# Eload_Gen_3_Power_Module_-_User_Inferfac.net
KiCad netlist of a schematic drawn in Altium Designer
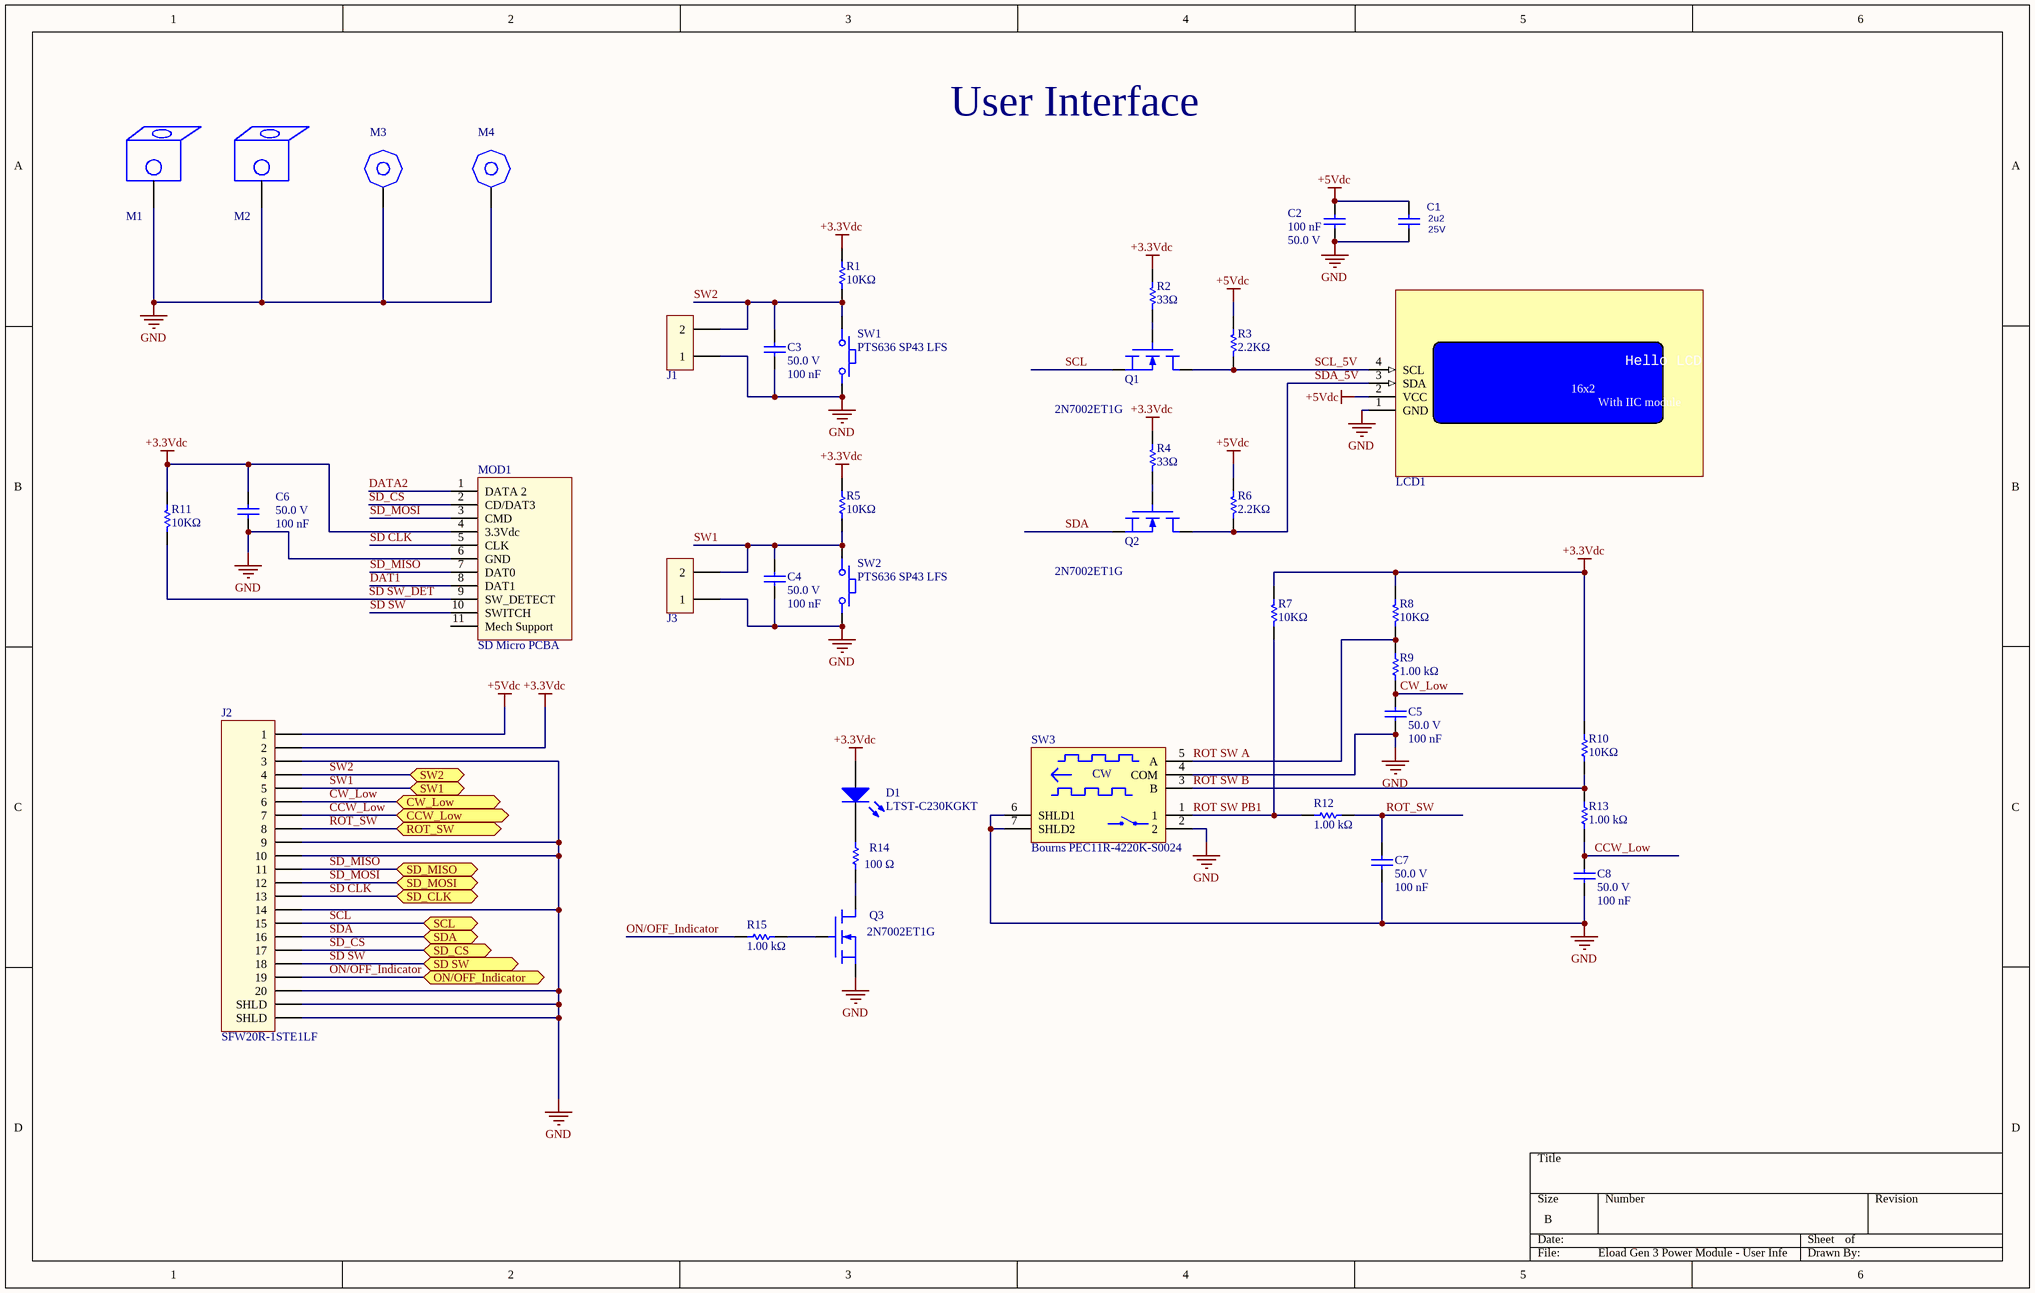
[diagram p0: Eload Gen 3 Power Module - User Inferface.SchDoc]

(export (version "E")
  (design (tool "Eeschema 10.0.6"))
  (components
    (comp (ref "C1")
      (value "2u2")
      (footprint "CAP, 0805, HD")
      (description "Cap,SMD,MLCC,2.2uF 25V X7R 10%,0805")
      (fields (field (name "MANUFACTURER") "Murata") (field (name "VOLTAGE") "25V"))
      (libsource (lib "Master SEPT2019") (part "Cap,0805,2.2uF,10%,25V"))
    )
    (comp (ref "C2")
      (value "08055C104JAT2A")
      (footprint "Cap,0805")
      (description "Capacitor; Ceramic; Cap 0.1 uF; Tol 5%; Vol-Rtg 50 VDC; SMT; 0805; X7R; Tape & Reel")
      (fields (field (name "VOLTAGE RATING (DC)") "50.0 V") (field (name "CAPACITANCE") "100 nF"))
      (libsource (lib "Master JULY2019") (part "Cap,0805,100nf,50V,5%,08055C104JAT2A"))
    )
    (comp (ref "C3")
      (value "08055C104JAT2A")
      (footprint "CAP, 0805, HD")
      (description "Capacitor; Ceramic; Cap 0.1 uF; Tol 5%; Vol-Rtg 50 VDC; SMT; 0805; X7R; Tape & Reel")
      (fields (field (name "VOLTAGE RATING (DC)") "50.0 V") (field (name "CAPACITANCE") "100 nF"))
      (libsource (lib "Master JULY2019") (part "Cap,0805,100nf,50V,5%,08055C104JAT2A"))
    )
    (comp (ref "C4")
      (value "08055C104JAT2A")
      (footprint "CAP, 0805, HD")
      (description "Capacitor; Ceramic; Cap 0.1 uF; Tol 5%; Vol-Rtg 50 VDC; SMT; 0805; X7R; Tape & Reel")
      (fields (field (name "VOLTAGE RATING (DC)") "50.0 V") (field (name "CAPACITANCE") "100 nF"))
      (libsource (lib "Master JULY2019") (part "Cap,0805,100nf,50V,5%,08055C104JAT2A"))
    )
    (comp (ref "C5")
      (value "08055C104JAT2A")
      (footprint "CAP, 0805, HD")
      (description "Capacitor; Ceramic; Cap 0.1 uF; Tol 5%; Vol-Rtg 50 VDC; SMT; 0805; X7R; Tape & Reel")
      (fields (field (name "VOLTAGE RATING (DC)") "50.0 V") (field (name "CAPACITANCE") "100 nF"))
      (libsource (lib "Master JULY2019") (part "Cap,0805,100nf,50V,5%,08055C104JAT2A"))
    )
    (comp (ref "C6")
      (value "08055C104JAT2A")
      (footprint "Cap,0805")
      (description "Capacitor; Ceramic; Cap 0.1 uF; Tol 5%; Vol-Rtg 50 VDC; SMT; 0805; X7R; Tape & Reel")
      (fields (field (name "VOLTAGE RATING (DC)") "50.0 V") (field (name "CAPACITANCE") "100 nF"))
      (libsource (lib "Master JULY2019") (part "Cap,0805,100nf,50V,5%,08055C104JAT2A"))
    )
    (comp (ref "C7")
      (value "08055C104JAT2A")
      (footprint "CAP, 0805, HD")
      (description "Capacitor; Ceramic; Cap 0.1 uF; Tol 5%; Vol-Rtg 50 VDC; SMT; 0805; X7R; Tape & Reel")
      (fields (field (name "VOLTAGE RATING (DC)") "50.0 V") (field (name "CAPACITANCE") "100 nF"))
      (libsource (lib "Master JULY2019") (part "Cap,0805,100nf,50V,5%,08055C104JAT2A"))
    )
    (comp (ref "C8")
      (value "08055C104JAT2A")
      (footprint "CAP, 0805, HD")
      (description "Capacitor; Ceramic; Cap 0.1 uF; Tol 5%; Vol-Rtg 50 VDC; SMT; 0805; X7R; Tape & Reel")
      (fields (field (name "VOLTAGE RATING (DC)") "50.0 V") (field (name "CAPACITANCE") "100 nF"))
      (libsource (lib "Master JULY2019") (part "Cap,0805,100nf,50V,5%,08055C104JAT2A"))
    )
    (comp (ref "D1")
      (value "LTST-C230KGKT")
      (footprint "LED,SMD,Bottom Entry,1206")
      (description "LED GREEN CLEAR CHIP SMD")
      (fields (field (name "MANUFACTURER") "Lite-On Inc."))
      (libsource (lib "Master JULY2019") (part "LED,1206,Green,SMD,BtmEnt,LTST-C230KGKT"))
    )
    (comp (ref "J1")
      (value "Generic Header")
      (footprint "HEADER-1X2,0.1\"")
      (libsource (lib "Master JULY2019") (part "Header 1x2,0.1{dblquote}Spacing"))
    )
    (comp (ref "J2")
      (value "SFW20R-1STE1LF")
      (footprint "Connector,FlatFlex,20Pin,RA")
      (description "CONN FFC BOTTOM 20POS 1.00MM R/A")
      (fields (field (name "MANUFACTURER") "Amphenol ICC (FCI)"))
      (libsource (lib "Master JULY2019") (part "Connector,FFC,SMD,20Pin,1mmSpc,SFW20R-1STE1LF"))
    )
    (comp (ref "J3")
      (value "Generic Header")
      (footprint "HEADER-1X2,0.1\"")
      (libsource (lib "Master JULY2019") (part "Header 1x2,0.1{dblquote}Spacing"))
    )
    (comp (ref "LCD1")
      (value "LCD, 20x4")
      (footprint "LCD Module 16x2 - IIC MOD")
      (description "LCD Character Display; 4x20 Char.; 98x60; STN- BLUE; Transmissive; 8-Bit Parallel")
      (libsource (lib "Master JULY2019") (part "LCD, 16x2, IIC"))
    )
    (comp (ref "M1")
      (value "4334")
      (footprint "Mech,Bracket,RA,#6,Threaded")
      (description "Mounting Bracket Short L #6-32 (2) Steel, Nickel Plated")
      (fields (field (name "MANUFACTURER") "Keystone Electronics"))
      (libsource (lib "Master JULY2019") (part "Mech,Bracket,RA,Threaded,4334"))
    )
    (comp (ref "M2")
      (value "4334")
      (footprint "Mech,Bracket,RA,#6,Threaded")
      (description "Mounting Bracket Short L #6-32 (2) Steel, Nickel Plated")
      (fields (field (name "MANUFACTURER") "Keystone Electronics"))
      (libsource (lib "Master JULY2019") (part "Mech,Bracket,RA,Threaded,4334"))
    )
    (comp (ref "M3")
      (value "M3 hex Standoff")
      (footprint "Standoff,Hex,M3,8mm")
      (description "HEX STANDOFF M3,generic")
      (libsource (lib "Master JULY2019") (part "Mech,Standoff, M3, Hex"))
    )
    (comp (ref "M4")
      (value "M3 hex Standoff")
      (footprint "Standoff,Hex,M3,8mm")
      (description "HEX STANDOFF M3,generic")
      (libsource (lib "Master JULY2019") (part "Mech,Standoff, M3, Hex"))
    )
    (comp (ref "MOD1")
      (value "SD Card Connector Breakout")
      (footprint "Mod, SD Card Connector Breakout")
      (fields (field (name "DISCRIPTION") "SD Micro PCBA"))
      (libsource (lib "Master JULY2019") (part "Mod,SD Card breakout, Vertical"))
    )
    (comp (ref "Q1")
      (value "2N7002ET1G")
      (footprint "SOT23-3")
      (description "Small Signal MOSFET, 60 V, 310 mA, Single, N-Channel, 3-Pin SOT-23, Pb-Free, Tape and Reel")
      (fields
        (field (name "MANUFACTURER") "ON Semiconductor")
        (field (name "MANUFACTURER PART NUMBER") "2N7002ET1G")
      )
      (libsource (lib "Master JULY2019") (part "MOSFET,N-Channel,SOT23,0.25A,60V,2N7002ET1G"))
    )
    (comp (ref "Q2")
      (value "2N7002ET1G")
      (footprint "SOT23-3")
      (description "Small Signal MOSFET, 60 V, 310 mA, Single, N-Channel, 3-Pin SOT-23, Pb-Free, Tape and Reel")
      (fields
        (field (name "MANUFACTURER") "ON Semiconductor")
        (field (name "MANUFACTURER PART NUMBER") "2N7002ET1G")
      )
      (libsource (lib "Master JULY2019") (part "MOSFET,N-Channel,SOT23,0.25A,60V,2N7002ET1G"))
    )
    (comp (ref "Q3")
      (value "2N7002ET1G")
      (footprint "SOT23-3")
      (description "Small Signal MOSFET, 60 V, 310 mA, Single, N-Channel, 3-Pin SOT-23, Pb-Free, Tape and Reel")
      (fields
        (field (name "MANUFACTURER") "ON Semiconductor")
        (field (name "MANUFACTURER PART NUMBER") "2N7002ET1G")
      )
      (libsource (lib "Master JULY2019") (part "MOSFET,N-Channel,SOT23,0.25A,60V,2N7002ET1G"))
    )
    (comp (ref "R1")
      (value "Vishay / Dale CRCW080510K0FKTA")
      (footprint "res, 0805, HD")
      (description "RES SMD 10K OHM 1% 1/8W 0805")
      (fields (field (name "RESISTANCE") "10KΩ"))
      (libsource (lib "Master JULY2019") (part "Res,0805,10.0kΩ,1%,100 ppm,CRCW080510K0FKTA"))
    )
    (comp (ref "R2")
      (value "CR0805-JW-330ELF")
      (footprint "res, 0805, HD")
      (description "RES SMD 33 OHM 5% 1/8W 0805")
      (fields
        (field (name "MANUFACTURER") "Bourns Inc.")
        (field (name "TOLERANCE") "±5%")
        (field (name "RESISTANCE") "33Ω")
      )
      (libsource (lib "Master JULY2019") (part "Res,0805,33Ω,±5%,200ppm,CR0805-JW-330ELF"))
    )
    (comp (ref "R3")
      (value "CRCW08052K20FKEA")
      (footprint "res, 0805, HD")
      (description "RES SMD 2.2K OHM 1% 1/8W 0805")
      (fields (field (name "RESISTANCE") "2.2KΩ"))
      (libsource (lib "Master JULY2019") (part "Res,0805,2.2KΩ,±1%,100.0 ppm/°C,150.0 V,CRCW08052K20FKEA"))
    )
    (comp (ref "R4")
      (value "CR0805-JW-330ELF")
      (footprint "res, 0805, HD")
      (description "RES SMD 33 OHM 5% 1/8W 0805")
      (fields
        (field (name "MANUFACTURER") "Bourns Inc.")
        (field (name "TOLERANCE") "±5%")
        (field (name "RESISTANCE") "33Ω")
      )
      (libsource (lib "Master JULY2019") (part "Res,0805,33Ω,±5%,200ppm,CR0805-JW-330ELF"))
    )
    (comp (ref "R5")
      (value "Vishay / Dale CRCW080510K0FKTA")
      (footprint "res, 0805, HD")
      (description "RES SMD 10K OHM 1% 1/8W 0805")
      (fields (field (name "RESISTANCE") "10KΩ"))
      (libsource (lib "Master JULY2019") (part "Res,0805,10.0kΩ,1%,100 ppm,CRCW080510K0FKTA"))
    )
    (comp (ref "R6")
      (value "CRCW08052K20FKEA")
      (footprint "res, 0805, HD")
      (description "RES SMD 2.2K OHM 1% 1/8W 0805")
      (fields (field (name "RESISTANCE") "2.2KΩ"))
      (libsource (lib "Master JULY2019") (part "Res,0805,2.2KΩ,±1%,100.0 ppm/°C,150.0 V,CRCW08052K20FKEA"))
    )
    (comp (ref "R7")
      (value "Vishay / Dale CRCW080510K0FKTA")
      (footprint "res, 0805, HD")
      (description "RES SMD 10K OHM 1% 1/8W 0805")
      (fields (field (name "RESISTANCE") "10KΩ"))
      (libsource (lib "Master JULY2019") (part "Res,0805,10.0kΩ,1%,100 ppm,CRCW080510K0FKTA"))
    )
    (comp (ref "R8")
      (value "Vishay / Dale CRCW080510K0FKTA")
      (footprint "res, 0805, HD")
      (description "RES SMD 10K OHM 1% 1/8W 0805")
      (fields (field (name "RESISTANCE") "10KΩ"))
      (libsource (lib "Master JULY2019") (part "Res,0805,10.0kΩ,1%,100 ppm,CRCW080510K0FKTA"))
    )
    (comp (ref "R9")
      (value "Vishay CRCW08051K00JNEA")
      (footprint "res, 0805, HD")
      (description "Res Thick Film 0805 1K Ohm 5% 0.125W(1/8W) ±200ppm/C Molded SMD Automotive Paper T/R")
      (fields
        (field (name "MANUFACTURER PART NUMBER") "CRCW08051K00JNEA")
        (field (name "RESISTANCE") "1.00 kΩ")
      )
      (libsource (lib "Master JULY2019") (part "Res,0805,1.00 kΩ,5%,200ppm,CRCW08051K00JNEA"))
    )
    (comp (ref "R10")
      (value "Vishay / Dale CRCW080510K0FKTA")
      (footprint "res, 0805, HD")
      (description "RES SMD 10K OHM 1% 1/8W 0805")
      (fields (field (name "RESISTANCE") "10KΩ"))
      (libsource (lib "Master JULY2019") (part "Res,0805,10.0kΩ,1%,100 ppm,CRCW080510K0FKTA"))
    )
    (comp (ref "R11")
      (value "Vishay / Dale CRCW080510K0FKTA")
      (footprint "res, 0805, HD")
      (description "RES SMD 10K OHM 1% 1/8W 0805")
      (fields (field (name "RESISTANCE") "10KΩ"))
      (libsource (lib "Master JULY2019") (part "Res,0805,10.0kΩ,1%,100 ppm,CRCW080510K0FKTA"))
    )
    (comp (ref "R12")
      (value "Vishay CRCW08051K00JNEA")
      (footprint "res, 0805, HD")
      (description "Res Thick Film 0805 1K Ohm 5% 0.125W(1/8W) ±200ppm/C Molded SMD Automotive Paper T/R")
      (fields
        (field (name "MANUFACTURER PART NUMBER") "CRCW08051K00JNEA")
        (field (name "RESISTANCE") "1.00 kΩ")
      )
      (libsource (lib "Master JULY2019") (part "Res,0805,1.00 kΩ,5%,200ppm,CRCW08051K00JNEA"))
    )
    (comp (ref "R13")
      (value "Vishay CRCW08051K00JNEA")
      (footprint "res, 0805, HD")
      (description "Res Thick Film 0805 1K Ohm 5% 0.125W(1/8W) ±200ppm/C Molded SMD Automotive Paper T/R")
      (fields
        (field (name "MANUFACTURER PART NUMBER") "CRCW08051K00JNEA")
        (field (name "RESISTANCE") "1.00 kΩ")
      )
      (libsource (lib "Master JULY2019") (part "Res,0805,1.00 kΩ,5%,200ppm,CRCW08051K00JNEA"))
    )
    (comp (ref "R14")
      (value "CRCW0805100RJNEAC")
      (footprint "res, 0805, HD")
      (description "RES 100 OHM 5% 1/8W 0805")
      (fields (field (name "TOLERANCE") "±5%") (field (name "RESISTANCE") "100 Ω"))
      (libsource (lib "Master JULY2019") (part "Res,0805,100Ω,5%,±200ppm/°C"))
    )
    (comp (ref "R15")
      (value "Vishay CRCW08051K00JNEA")
      (footprint "res, 0805, HD")
      (description "Res Thick Film 0805 1K Ohm 5% 0.125W(1/8W) ±200ppm/C Molded SMD Automotive Paper T/R")
      (fields
        (field (name "MANUFACTURER PART NUMBER") "CRCW08051K00JNEA")
        (field (name "RESISTANCE") "1.00 kΩ")
      )
      (libsource (lib "Master JULY2019") (part "Res,0805,1.00 kΩ,5%,200ppm,CRCW08051K00JNEA"))
    )
    (comp (ref "SW1")
      (value "PTS636 SP43 LFS")
      (footprint "PTS636 SP43 LFS")
      (description "Tactile Switch SPST-NO Top Actuated Through Hole")
      (fields (field (name "MANUFACTURER") "C&K"))
      (libsource (lib "Master JULY2019") (part "Switch,Through Hole,Tactile,SPST-NO,PTS636 SP43 LFS"))
    )
    (comp (ref "SW2")
      (value "PTS636 SP43 LFS")
      (footprint "PTS636 SP43 LFS")
      (description "Tactile Switch SPST-NO Top Actuated Through Hole")
      (fields (field (name "MANUFACTURER") "C&K"))
      (libsource (lib "Master JULY2019") (part "Switch,Through Hole,Tactile,SPST-NO,PTS636 SP43 LFS"))
    )
    (comp (ref "SW3")
      (value "Bourns PEC11R-4220K-S0024")
      (footprint "Rotary encoder")
      (description "24 Pulse Incremental Mechanical Rotary Encoder w/ 6 mm Knurl Shaft, Through Hole")
      (libsource (lib "Master JULY2019") (part "Rotary encoder, PEC11R-4220K-S0024"))
    )
  )
  (nets
    (net (code "1") (name "+3.3Vdc") (class "Default")
      (node (ref "C6") (pin "2") (pinfunction "2_2") (pintype "passive"))
      (node (ref "D1") (pin "2") (pinfunction "A_2") (pintype "passive"))
      (node (ref "J2") (pin "2") (pinfunction "2_2") (pintype "passive"))
      (node (ref "MOD1") (pin "4") (pinfunction "3.3Vdc_4") (pintype "passive"))
      (node (ref "R1") (pin "1") (pinfunction "1_1") (pintype "passive"))
      (node (ref "R10") (pin "1") (pinfunction "1_1") (pintype "passive"))
      (node (ref "R11") (pin "1") (pinfunction "1_1") (pintype "passive"))
      (node (ref "R2") (pin "1") (pinfunction "1_1") (pintype "passive"))
      (node (ref "R4") (pin "1") (pinfunction "1_1") (pintype "passive"))
      (node (ref "R5") (pin "1") (pinfunction "1_1") (pintype "passive"))
      (node (ref "R7") (pin "2") (pinfunction "2_2") (pintype "passive"))
      (node (ref "R8") (pin "2") (pinfunction "2_2") (pintype "passive"))
    )
    (net (code "2") (name "+5Vdc") (class "Default")
      (node (ref "C1") (pin "2") (pintype "passive"))
      (node (ref "C2") (pin "2") (pinfunction "2_2") (pintype "passive"))
      (node (ref "J2") (pin "1") (pinfunction "1_1") (pintype "passive"))
      (node (ref "LCD1") (pin "2") (pinfunction "VCC_2") (pintype "power_in"))
      (node (ref "R3") (pin "2") (pinfunction "2_2") (pintype "passive"))
      (node (ref "R6") (pin "2") (pinfunction "2_2") (pintype "passive"))
    )
    (net (code "3") (name "/CCW_Low") (class "Default")
      (node (ref "C8") (pin "2") (pinfunction "2_2") (pintype "passive"))
      (node (ref "J2") (pin "7") (pinfunction "7_7") (pintype "passive"))
      (node (ref "R13") (pin "2") (pinfunction "2_2") (pintype "passive"))
    )
    (net (code "4") (name "/CW_Low") (class "Default")
      (node (ref "C5") (pin "2") (pinfunction "2_2") (pintype "passive"))
      (node (ref "J2") (pin "6") (pinfunction "6_6") (pintype "passive"))
      (node (ref "R9") (pin "2") (pinfunction "2_2") (pintype "passive"))
    )
    (net (code "5") (name "/DAT1") (class "Default")
      (node (ref "MOD1") (pin "8") (pinfunction "DAT1_8") (pintype "passive"))
    )
    (net (code "6") (name "/DATA2") (class "Default")
      (node (ref "MOD1") (pin "1") (pinfunction "DATA_2_1") (pintype "passive"))
    )
    (net (code "7") (name "/ON{slash}OFF_Indicator") (class "Default")
      (node (ref "J2") (pin "19") (pinfunction "19_19") (pintype "passive"))
      (node (ref "R15") (pin "1") (pinfunction "1_1") (pintype "passive"))
    )
    (net (code "8") (name "/ROT SW A") (class "Default")
      (node (ref "R8") (pin "1") (pinfunction "1_1") (pintype "passive"))
      (node (ref "R9") (pin "1") (pinfunction "1_1") (pintype "passive"))
      (node (ref "SW3") (pin "5") (pinfunction "A_5") (pintype "passive"))
    )
    (net (code "9") (name "/ROT SW B") (class "Default")
      (node (ref "R10") (pin "2") (pinfunction "2_2") (pintype "passive"))
      (node (ref "R13") (pin "1") (pinfunction "1_1") (pintype "passive"))
      (node (ref "SW3") (pin "3") (pinfunction "B_3") (pintype "passive"))
    )
    (net (code "10") (name "/ROT SW PB1") (class "Default")
      (node (ref "R12") (pin "1") (pinfunction "1_1") (pintype "passive"))
      (node (ref "R7") (pin "1") (pinfunction "1_1") (pintype "passive"))
      (node (ref "SW3") (pin "1") (pinfunction "1_1") (pintype "passive"))
    )
    (net (code "11") (name "/ROT_SW") (class "Default")
      (node (ref "C7") (pin "2") (pinfunction "2_2") (pintype "passive"))
      (node (ref "J2") (pin "8") (pinfunction "8_8") (pintype "passive"))
      (node (ref "R12") (pin "2") (pinfunction "2_2") (pintype "passive"))
    )
    (net (code "12") (name "/SCL") (class "Default")
      (node (ref "J2") (pin "15") (pinfunction "15_15") (pintype "passive"))
      (node (ref "Q1") (pin "2") (pinfunction "S_2") (pintype "passive"))
    )
    (net (code "13") (name "/SCL_5V") (class "Default")
      (node (ref "LCD1") (pin "4") (pinfunction "SCL_4") (pintype "input"))
      (node (ref "Q1") (pin "3") (pinfunction "D_3") (pintype "passive"))
      (node (ref "R3") (pin "1") (pinfunction "1_1") (pintype "passive"))
    )
    (net (code "14") (name "/SD CLK") (class "Default")
      (node (ref "J2") (pin "13") (pinfunction "13_13") (pintype "passive"))
      (node (ref "MOD1") (pin "5") (pinfunction "CLK_5") (pintype "passive"))
    )
    (net (code "15") (name "/SD SW") (class "Default")
      (node (ref "J2") (pin "18") (pinfunction "18_18") (pintype "passive"))
      (node (ref "MOD1") (pin "10") (pinfunction "SWITCH_10") (pintype "passive"))
    )
    (net (code "16") (name "/SD SW_DET") (class "Default")
      (node (ref "MOD1") (pin "9") (pinfunction "SW_DETECT_9") (pintype "passive"))
      (node (ref "R11") (pin "2") (pinfunction "2_2") (pintype "passive"))
    )
    (net (code "17") (name "/SDA") (class "Default")
      (node (ref "J2") (pin "16") (pinfunction "16_16") (pintype "passive"))
      (node (ref "Q2") (pin "2") (pinfunction "S_2") (pintype "passive"))
    )
    (net (code "18") (name "/SDA_5V") (class "Default")
      (node (ref "LCD1") (pin "3") (pinfunction "SDA_3") (pintype "input"))
      (node (ref "Q2") (pin "3") (pinfunction "D_3") (pintype "passive"))
      (node (ref "R6") (pin "1") (pinfunction "1_1") (pintype "passive"))
    )
    (net (code "19") (name "/SD_CS") (class "Default")
      (node (ref "J2") (pin "17") (pinfunction "17_17") (pintype "passive"))
      (node (ref "MOD1") (pin "2") (pinfunction "CD/DAT3_2") (pintype "passive"))
    )
    (net (code "20") (name "/SD_MISO") (class "Default")
      (node (ref "J2") (pin "11") (pinfunction "11_11") (pintype "passive"))
      (node (ref "MOD1") (pin "7") (pinfunction "DAT0_7") (pintype "passive"))
    )
    (net (code "21") (name "/SD_MOSI") (class "Default")
      (node (ref "J2") (pin "12") (pinfunction "12_12") (pintype "passive"))
      (node (ref "MOD1") (pin "3") (pinfunction "CMD_3") (pintype "passive"))
    )
    (net (code "22") (name "/SW1") (class "Default")
      (node (ref "C4") (pin "2") (pinfunction "2_2") (pintype "passive"))
      (node (ref "J2") (pin "5") (pinfunction "5_5") (pintype "passive"))
      (node (ref "J3") (pin "2") (pinfunction "2_2") (pintype "passive"))
      (node (ref "R5") (pin "2") (pinfunction "2_2") (pintype "passive"))
      (node (ref "SW2") (pin "1") (pinfunction "1_1") (pintype "passive"))
    )
    (net (code "23") (name "/SW2") (class "Default")
      (node (ref "C3") (pin "2") (pinfunction "2_2") (pintype "passive"))
      (node (ref "J1") (pin "2") (pinfunction "2_2") (pintype "passive"))
      (node (ref "J2") (pin "4") (pinfunction "4_4") (pintype "passive"))
      (node (ref "R1") (pin "2") (pinfunction "2_2") (pintype "passive"))
      (node (ref "SW1") (pin "1") (pinfunction "1_1") (pintype "passive"))
    )
    (net (code "24") (name "GND") (class "Default")
      (node (ref "C1") (pin "1") (pintype "passive"))
      (node (ref "C2") (pin "1") (pinfunction "1_1") (pintype "passive"))
      (node (ref "C3") (pin "1") (pinfunction "1_1") (pintype "passive"))
      (node (ref "C4") (pin "1") (pinfunction "1_1") (pintype "passive"))
      (node (ref "C5") (pin "1") (pinfunction "1_1") (pintype "passive"))
      (node (ref "C6") (pin "1") (pinfunction "1_1") (pintype "passive"))
      (node (ref "C7") (pin "1") (pinfunction "1_1") (pintype "passive"))
      (node (ref "C8") (pin "1") (pinfunction "1_1") (pintype "passive"))
      (node (ref "J1") (pin "1") (pinfunction "1_1") (pintype "passive"))
      (node (ref "J2") (pin "10") (pinfunction "10_10") (pintype "passive"))
      (node (ref "J2") (pin "14") (pinfunction "14_14") (pintype "passive"))
      (node (ref "J2") (pin "20") (pinfunction "20_20") (pintype "passive"))
      (node (ref "J2") (pin "21") (pinfunction "SHLD_21") (pintype "passive"))
      (node (ref "J2") (pin "22") (pinfunction "SHLD_22") (pintype "passive"))
      (node (ref "J2") (pin "3") (pinfunction "3_3") (pintype "passive"))
      (node (ref "J2") (pin "9") (pinfunction "9_9") (pintype "passive"))
      (node (ref "J3") (pin "1") (pinfunction "1_1") (pintype "passive"))
      (node (ref "LCD1") (pin "1") (pinfunction "GND_1") (pintype "power_in"))
      (node (ref "M1") (pin "1") (pinfunction "1_1") (pintype "passive"))
      (node (ref "M2") (pin "1") (pinfunction "1_1") (pintype "passive"))
      (node (ref "M3") (pin "0") (pinfunction "0_0") (pintype "passive"))
      (node (ref "M4") (pin "0") (pinfunction "0_0") (pintype "passive"))
      (node (ref "MOD1") (pin "6") (pinfunction "GND_6") (pintype "passive"))
      (node (ref "Q3") (pin "2") (pinfunction "S_2") (pintype "passive"))
      (node (ref "SW1") (pin "2") (pinfunction "2_2") (pintype "passive"))
      (node (ref "SW2") (pin "2") (pinfunction "2_2") (pintype "passive"))
      (node (ref "SW3") (pin "2") (pinfunction "2_2") (pintype "passive"))
      (node (ref "SW3") (pin "4") (pinfunction "COM_4") (pintype "passive"))
      (node (ref "SW3") (pin "6") (pinfunction "SHLD1_6") (pintype "passive"))
      (node (ref "SW3") (pin "7") (pinfunction "SHLD2_7") (pintype "passive"))
    )
    (net (code "25") (name "Net-(D1-K)") (class "Default")
      (node (ref "D1") (pin "1") (pinfunction "K_1") (pintype "passive"))
      (node (ref "R14") (pin "2") (pinfunction "2_2") (pintype "passive"))
    )
    (net (code "26") (name "Net-(Q1-G)") (class "Default")
      (node (ref "Q1") (pin "1") (pinfunction "G_1") (pintype "passive"))
      (node (ref "R2") (pin "2") (pinfunction "2_2") (pintype "passive"))
    )
    (net (code "27") (name "Net-(Q2-G)") (class "Default")
      (node (ref "Q2") (pin "1") (pinfunction "G_1") (pintype "passive"))
      (node (ref "R4") (pin "2") (pinfunction "2_2") (pintype "passive"))
    )
    (net (code "28") (name "Net-(Q3-D)") (class "Default")
      (node (ref "Q3") (pin "3") (pinfunction "D_3") (pintype "passive"))
      (node (ref "R14") (pin "1") (pinfunction "1_1") (pintype "passive"))
    )
    (net (code "29") (name "Net-(Q3-G)") (class "Default")
      (node (ref "Q3") (pin "1") (pinfunction "G_1") (pintype "passive"))
      (node (ref "R15") (pin "2") (pinfunction "2_2") (pintype "passive"))
    )
    (net (code "30") (name "unconnected-(MOD1-Mech_Support-Pad11)") (class "Default")
      (node (ref "MOD1") (pin "11") (pinfunction "Mech_Support_11") (pintype "passive"))
    )
  )
)
